# Counter.net
KiCad netlist of a schematic drawn in EAGLE
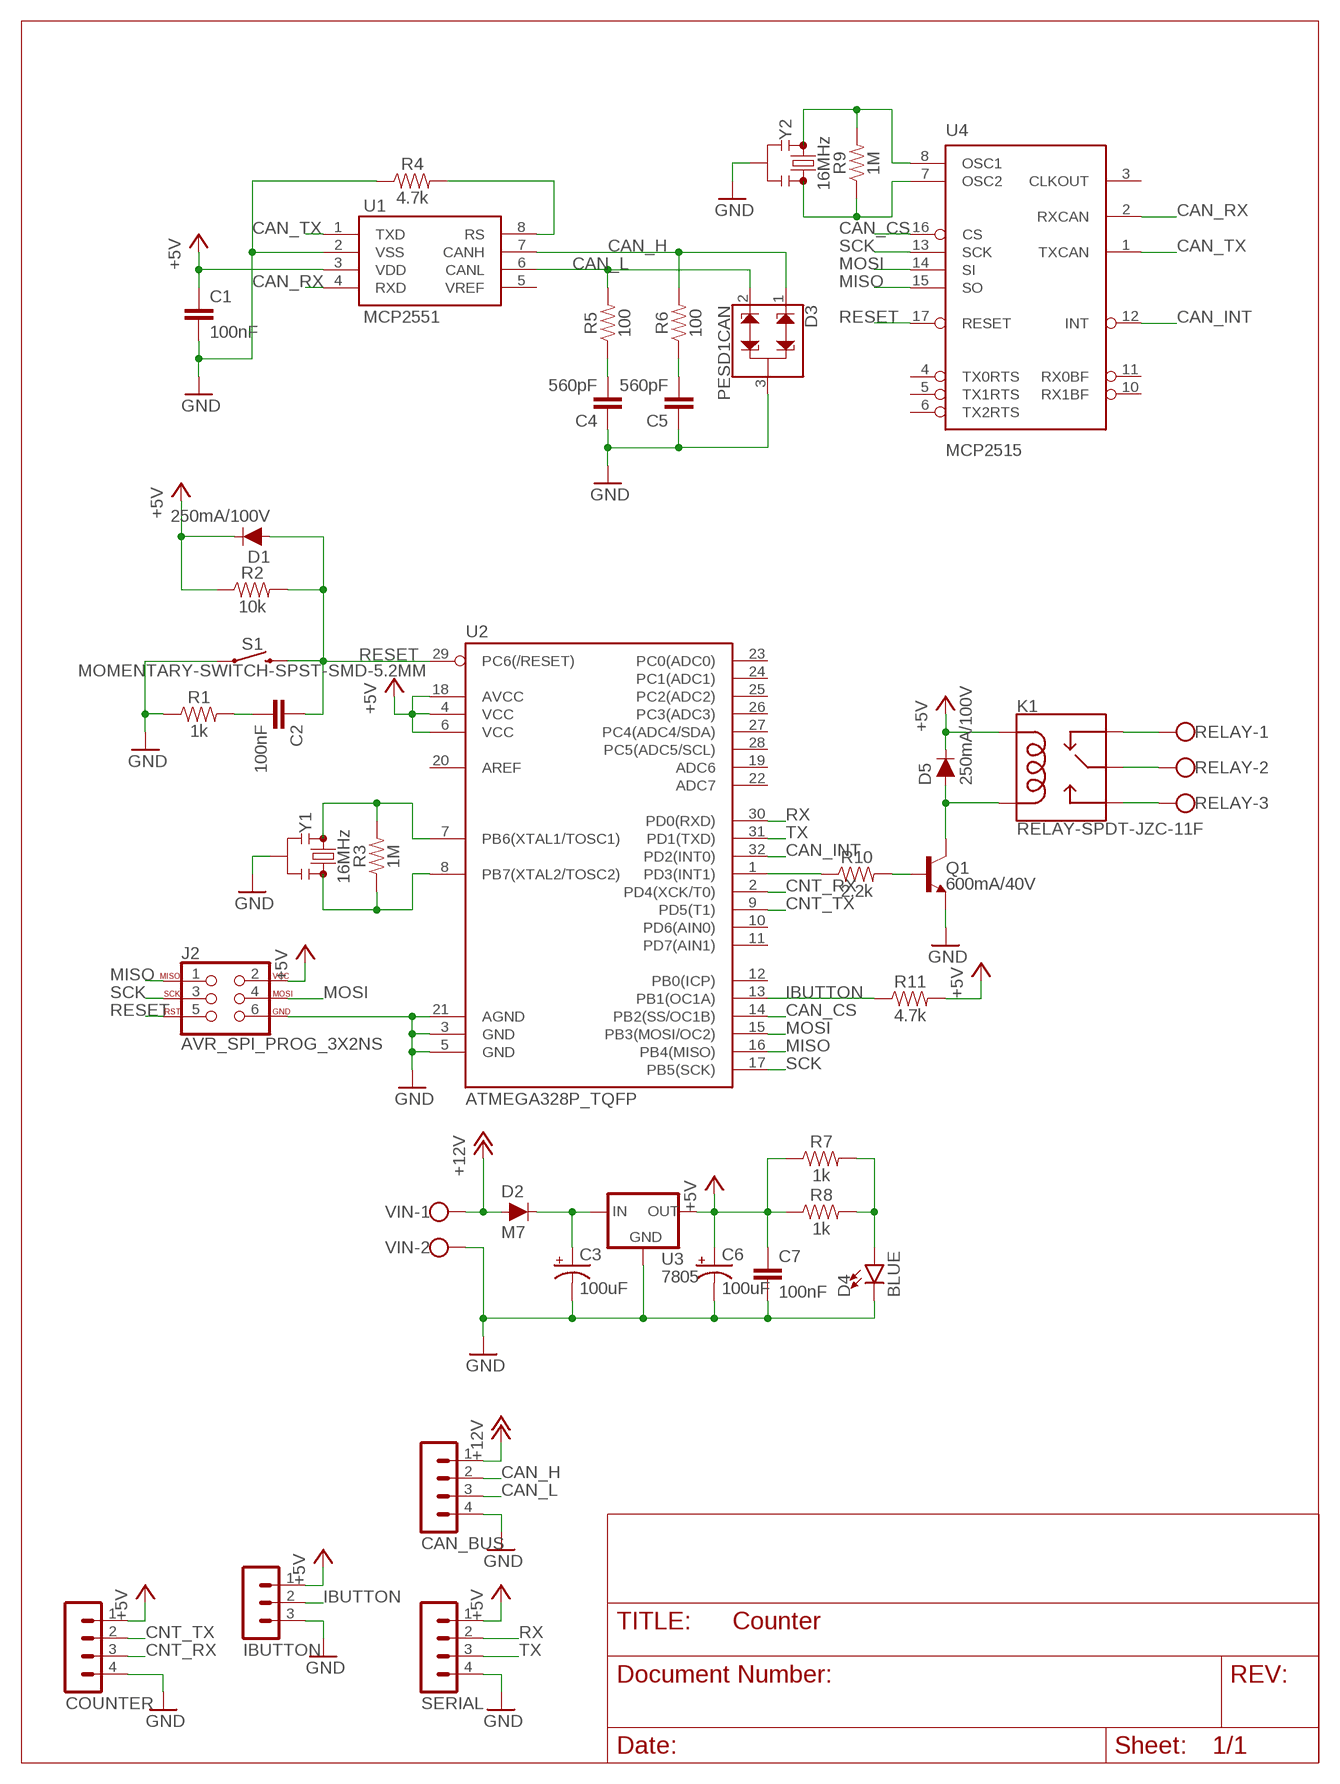
[diagram p0: schematic, sheet 1]

(export (version "E")
  (design (tool "Eeschema 10.0.6"))
  (components
    (comp (ref "C1")
      (value "100nF")
      (footprint "eagle-import:0603")
      (libsource (lib "eagle-import") (part "47NF-0603-25V-5%"))
    )
    (comp (ref "C2")
      (value "100nF")
      (footprint "eagle-import:0603")
      (libsource (lib "eagle-import") (part "47NF-0603-25V-5%"))
    )
    (comp (ref "C3")
      (value "100uF")
      (footprint "eagle-import:PANASONIC_D")
      (libsource (lib "eagle-import") (part "47UF-POLAR-PANASONIC_D-35V-20%"))
    )
    (comp (ref "C4")
      (value "560pF")
      (footprint "eagle-import:0603")
      (libsource (lib "eagle-import") (part "560PF-0603-50V-5%"))
    )
    (comp (ref "C5")
      (value "560pF")
      (footprint "eagle-import:0603")
      (libsource (lib "eagle-import") (part "560PF-0603-50V-5%"))
    )
    (comp (ref "C6")
      (value "100uF")
      (footprint "eagle-import:PANASONIC_D")
      (libsource (lib "eagle-import") (part "47UF-POLAR-PANASONIC_D-35V-20%"))
    )
    (comp (ref "C7")
      (value "100nF")
      (footprint "eagle-import:0603")
      (libsource (lib "eagle-import") (part "47NF-0603-25V-5%"))
    )
    (comp (ref "CAN_BUS")
      (value "MA04-1")
      (footprint "eagle-import:MA04-1")
      (libsource (lib "eagle-import") (part "MA04-1"))
    )
    (comp (ref "COUNTER")
      (value "MA04-1")
      (footprint "eagle-import:MA04-1")
      (libsource (lib "eagle-import") (part "MA04-1"))
    )
    (comp (ref "D1")
      (value "250mA/100V")
      (footprint "eagle-import:SOD-323")
      (libsource (lib "eagle-import") (part "DIODE-BAS16J"))
    )
    (comp (ref "D2")
      (value "M7")
      (footprint "eagle-import:SOD-323")
      (libsource (lib "eagle-import") (part "DIODE-BAS16J"))
    )
    (comp (ref "D3")
      (value "PESD1CAN")
      (footprint "eagle-import:SOT23-3")
      (libsource (lib "eagle-import") (part "PESD1CAN"))
    )
    (comp (ref "D4")
      (value "BLUE")
      (footprint "eagle-import:LED-0603")
      (libsource (lib "eagle-import") (part "LED-BLUE0603"))
    )
    (comp (ref "D5")
      (value "250mA/100V")
      (footprint "eagle-import:SOD-323")
      (libsource (lib "eagle-import") (part "DIODE-BAS16J"))
    )
    (comp (ref "IBUTTON")
      (value "MA03-1")
      (footprint "eagle-import:MA03-1")
      (libsource (lib "eagle-import") (part "MA03-1"))
    )
    (comp (ref "J2")
      (value "AVR_SPI_PROG_3X2NS")
      (footprint "eagle-import:2X3-NS")
      (libsource (lib "eagle-import") (part "AVR_SPI_PROG_3X2NS"))
    )
    (comp (ref "K1")
      (value "RELAY-SPDT-JZC-11F")
      (footprint "eagle-import:RELAY-JZC")
      (libsource (lib "eagle-import") (part "RELAY-SPDT-JZC-11F"))
    )
    (comp (ref "Q1")
      (value "600mA/40V")
      (footprint "eagle-import:SOT23-3")
      (libsource (lib "eagle-import") (part "TRANS_NPN-MMBT2222AL"))
    )
    (comp (ref "R1")
      (value "1k")
      (footprint "eagle-import:0603")
      (libsource (lib "eagle-import") (part "1KOHM-0603-1/10W-1%"))
    )
    (comp (ref "R2")
      (value "10k")
      (footprint "eagle-import:0603")
      (libsource (lib "eagle-import") (part "10KOHM-0603-1/10W-1%"))
    )
    (comp (ref "R3")
      (value "1M")
      (footprint "eagle-import:0603")
      (libsource (lib "eagle-import") (part "1MOHM-0603-1/4W-5%"))
    )
    (comp (ref "R4")
      (value "4.7k")
      (footprint "eagle-import:0603")
      (libsource (lib "eagle-import") (part "4.7KOHM-0603-1/10W-1%"))
    )
    (comp (ref "R5")
      (value "100")
      (footprint "eagle-import:0603")
      (libsource (lib "eagle-import") (part "100OHM-0603-1/10W-1%"))
    )
    (comp (ref "R6")
      (value "100")
      (footprint "eagle-import:0603")
      (libsource (lib "eagle-import") (part "100OHM-0603-1/10W-1%"))
    )
    (comp (ref "R7")
      (value "1k")
      (footprint "eagle-import:0603")
      (libsource (lib "eagle-import") (part "1KOHM-0603-1/10W-1%"))
    )
    (comp (ref "R8")
      (value "1k")
      (footprint "eagle-import:0603")
      (libsource (lib "eagle-import") (part "1KOHM-0603-1/10W-1%"))
    )
    (comp (ref "R9")
      (value "1M")
      (footprint "eagle-import:0603")
      (libsource (lib "eagle-import") (part "1MOHM-0603-1/4W-5%"))
    )
    (comp (ref "R10")
      (value "2.2k")
      (footprint "eagle-import:0603")
      (libsource (lib "eagle-import") (part "2.2KOHM-0603-1/10W-1%"))
    )
    (comp (ref "R11")
      (value "4.7k")
      (footprint "eagle-import:0603")
      (libsource (lib "eagle-import") (part "4.7KOHM-0603-1/10W-1%"))
    )
    (comp (ref "RELAY")
      (value "W237-103")
      (footprint "eagle-import:W237-103")
      (fields (field (name "MPN") "237-103"))
      (libsource (lib "eagle-import") (part "W237-103"))
    )
    (comp (ref "S1")
      (value "MOMENTARY-SWITCH-SPST-SMD-5.2MM")
      (footprint "eagle-import:TACTILE_SWITCH_SMD_5.2MM")
      (libsource (lib "eagle-import") (part "MOMENTARY-SWITCH-SPST-SMD-5.2MM"))
    )
    (comp (ref "SERIAL")
      (value "MA04-1")
      (footprint "eagle-import:MA04-1")
      (libsource (lib "eagle-import") (part "MA04-1"))
    )
    (comp (ref "U1")
      (value "MCP2551")
      (footprint "eagle-import:SO08")
      (libsource (lib "eagle-import") (part "MCP2551"))
    )
    (comp (ref "U2")
      (value "ATMEGA328P_TQFP")
      (footprint "eagle-import:TQFP32-08")
      (libsource (lib "eagle-import") (part "ATMEGA328P_TQFP"))
    )
    (comp (ref "U3")
      (value "7805")
      (footprint "eagle-import:TO-252")
      (libsource (lib "eagle-import") (part "V_REG_78XX7812"))
    )
    (comp (ref "U4")
      (value "MCP2515")
      (footprint "eagle-import:SO18W")
      (libsource (lib "eagle-import") (part "MCP2515(MCP2510)SO"))
    )
    (comp (ref "VIN")
      (value "W237-102")
      (footprint "eagle-import:W237-102")
      (fields (field (name "MPN") "237-102"))
      (libsource (lib "eagle-import") (part "W237-102"))
    )
    (comp (ref "Y1")
      (value "16MHz")
      (footprint "eagle-import:RESONATOR-SMD-3.2X1.3")
      (libsource (lib "eagle-import") (part "RESONATOR-16MHZSMD_3.2X1.3"))
    )
    (comp (ref "Y2")
      (value "16MHz")
      (footprint "eagle-import:RESONATOR-SMD-3.2X1.3")
      (libsource (lib "eagle-import") (part "RESONATOR-16MHZSMD_3.2X1.3"))
    )
  )
  (nets
    (net (code "1") (name "+5V") (class "Default")
      (node (ref "C1") (pin "1") (pinfunction "1_1") (pintype "passive"))
      (node (ref "C6") (pin "+") (pinfunction "+_+") (pintype "passive"))
      (node (ref "C7") (pin "1") (pinfunction "1_1") (pintype "passive"))
      (node (ref "COUNTER") (pin "1") (pinfunction "1_1") (pintype "passive"))
      (node (ref "D1") (pin "C") (pinfunction "C_C") (pintype "passive"))
      (node (ref "D5") (pin "C") (pinfunction "C_C") (pintype "passive"))
      (node (ref "IBUTTON") (pin "1") (pinfunction "1_1") (pintype "passive"))
      (node (ref "J2") (pin "2") (pinfunction "2_2") (pintype "passive"))
      (node (ref "K1") (pin "5") (pinfunction "COIL1_5") (pintype "bidirectional"))
      (node (ref "R11") (pin "2") (pinfunction "2_2") (pintype "passive"))
      (node (ref "R2") (pin "1") (pinfunction "1_1") (pintype "passive"))
      (node (ref "R7") (pin "1") (pinfunction "1_1") (pintype "passive"))
      (node (ref "R8") (pin "1") (pinfunction "1_1") (pintype "passive"))
      (node (ref "SERIAL") (pin "1") (pinfunction "1_1") (pintype "passive"))
      (node (ref "U1") (pin "3") (pinfunction "VDD_3") (pintype "bidirectional"))
      (node (ref "U2") (pin "18") (pinfunction "AVCC_18") (pintype "bidirectional"))
      (node (ref "U2") (pin "4") (pinfunction "VCC_4") (pintype "bidirectional"))
      (node (ref "U2") (pin "6") (pinfunction "VCC_6") (pintype "bidirectional"))
      (node (ref "U3") (pin "2") (pinfunction "OUT_2") (pintype "passive"))
    )
    (net (code "2") (name "+12V") (class "Default")
      (node (ref "CAN_BUS") (pin "1") (pinfunction "1_1") (pintype "passive"))
      (node (ref "D2") (pin "A") (pinfunction "A_A") (pintype "passive"))
      (node (ref "VIN") (pin "1") (pinfunction "KL_1") (pintype "passive"))
    )
    (net (code "3") (name "/CAN_CS") (class "Default")
      (node (ref "U2") (pin "14") (pinfunction "PB2(SS/OC1B)_14") (pintype "bidirectional"))
      (node (ref "U4") (pin "16") (pinfunction "CS_16") (pintype "input"))
    )
    (net (code "4") (name "/CAN_H") (class "Default")
      (node (ref "CAN_BUS") (pin "2") (pinfunction "2_2") (pintype "passive"))
      (node (ref "D3") (pin "1") (pinfunction "1_1") (pintype "bidirectional"))
      (node (ref "R6") (pin "2") (pinfunction "2_2") (pintype "passive"))
      (node (ref "U1") (pin "7") (pinfunction "CANH_7") (pintype "bidirectional"))
    )
    (net (code "5") (name "/CAN_INT") (class "Default")
      (node (ref "U2") (pin "32") (pinfunction "PD2(INT0)_32") (pintype "bidirectional"))
      (node (ref "U4") (pin "12") (pinfunction "INT_12") (pintype "output"))
    )
    (net (code "6") (name "/CAN_L") (class "Default")
      (node (ref "CAN_BUS") (pin "3") (pinfunction "3_3") (pintype "passive"))
      (node (ref "D3") (pin "2") (pinfunction "2_2") (pintype "bidirectional"))
      (node (ref "R5") (pin "2") (pinfunction "2_2") (pintype "passive"))
      (node (ref "U1") (pin "6") (pinfunction "CANL_6") (pintype "bidirectional"))
    )
    (net (code "7") (name "/CAN_RX") (class "Default")
      (node (ref "U1") (pin "4") (pinfunction "RXD_4") (pintype "bidirectional"))
      (node (ref "U4") (pin "2") (pinfunction "RXCAN_2") (pintype "input"))
    )
    (net (code "8") (name "/CAN_TX") (class "Default")
      (node (ref "U1") (pin "1") (pinfunction "TXD_1") (pintype "bidirectional"))
      (node (ref "U4") (pin "1") (pinfunction "TXCAN_1") (pintype "output"))
    )
    (net (code "9") (name "/CNT_RX") (class "Default")
      (node (ref "COUNTER") (pin "3") (pinfunction "3_3") (pintype "passive"))
      (node (ref "U2") (pin "2") (pinfunction "PD4(XCK/T0)_2") (pintype "bidirectional"))
    )
    (net (code "10") (name "/CNT_TX") (class "Default")
      (node (ref "COUNTER") (pin "2") (pinfunction "2_2") (pintype "passive"))
      (node (ref "U2") (pin "9") (pinfunction "PD5(T1)_9") (pintype "bidirectional"))
    )
    (net (code "11") (name "/IBUTTON") (class "Default")
      (node (ref "IBUTTON") (pin "2") (pinfunction "2_2") (pintype "passive"))
      (node (ref "R11") (pin "1") (pinfunction "1_1") (pintype "passive"))
      (node (ref "U2") (pin "13") (pinfunction "PB1(OC1A)_13") (pintype "bidirectional"))
    )
    (net (code "12") (name "/MISO") (class "Default")
      (node (ref "J2") (pin "1") (pinfunction "1_1") (pintype "passive"))
      (node (ref "U2") (pin "16") (pinfunction "PB4(MISO)_16") (pintype "bidirectional"))
      (node (ref "U4") (pin "15") (pinfunction "SO_15") (pintype "output"))
    )
    (net (code "13") (name "/MOSI") (class "Default")
      (node (ref "J2") (pin "4") (pinfunction "4_4") (pintype "passive"))
      (node (ref "U2") (pin "15") (pinfunction "PB3(MOSI/OC2)_15") (pintype "bidirectional"))
      (node (ref "U4") (pin "14") (pinfunction "SI_14") (pintype "input"))
    )
    (net (code "14") (name "/RESET") (class "Default")
      (node (ref "C2") (pin "1") (pinfunction "1_1") (pintype "passive"))
      (node (ref "D1") (pin "A") (pinfunction "A_A") (pintype "passive"))
      (node (ref "J2") (pin "5") (pinfunction "5_5") (pintype "passive"))
      (node (ref "R2") (pin "2") (pinfunction "2_2") (pintype "passive"))
      (node (ref "S1") (pin "3") (pinfunction "2_3") (pintype "passive"))
      (node (ref "U2") (pin "29") (pinfunction "PC6(/RESET)_29") (pintype "bidirectional"))
      (node (ref "U4") (pin "17") (pinfunction "RESET_17") (pintype "input"))
    )
    (net (code "15") (name "/RX") (class "Default")
      (node (ref "SERIAL") (pin "2") (pinfunction "2_2") (pintype "passive"))
      (node (ref "U2") (pin "30") (pinfunction "PD0(RXD)_30") (pintype "bidirectional"))
    )
    (net (code "16") (name "/SCK") (class "Default")
      (node (ref "J2") (pin "3") (pinfunction "3_3") (pintype "passive"))
      (node (ref "U2") (pin "17") (pinfunction "PB5(SCK)_17") (pintype "bidirectional"))
      (node (ref "U4") (pin "13") (pinfunction "SCK_13") (pintype "input"))
    )
    (net (code "17") (name "/TX") (class "Default")
      (node (ref "SERIAL") (pin "3") (pinfunction "3_3") (pintype "passive"))
      (node (ref "U2") (pin "31") (pinfunction "PD1(TXD)_31") (pintype "bidirectional"))
    )
    (net (code "18") (name "GND") (class "Default")
      (node (ref "C1") (pin "2") (pinfunction "2_2") (pintype "passive"))
      (node (ref "C3") (pin "-") (pinfunction "-_-") (pintype "passive"))
      (node (ref "C4") (pin "1") (pinfunction "1_1") (pintype "passive"))
      (node (ref "C5") (pin "1") (pinfunction "1_1") (pintype "passive"))
      (node (ref "C6") (pin "-") (pinfunction "-_-") (pintype "passive"))
      (node (ref "C7") (pin "2") (pinfunction "2_2") (pintype "passive"))
      (node (ref "CAN_BUS") (pin "4") (pinfunction "4_4") (pintype "passive"))
      (node (ref "COUNTER") (pin "4") (pinfunction "4_4") (pintype "passive"))
      (node (ref "D3") (pin "3") (pinfunction "3_3") (pintype "bidirectional"))
      (node (ref "D4") (pin "C") (pinfunction "C_C") (pintype "passive"))
      (node (ref "IBUTTON") (pin "3") (pinfunction "3_3") (pintype "passive"))
      (node (ref "J2") (pin "6") (pinfunction "6_6") (pintype "passive"))
      (node (ref "Q1") (pin "2") (pinfunction "E_2") (pintype "passive"))
      (node (ref "R1") (pin "1") (pinfunction "1_1") (pintype "passive"))
      (node (ref "R4") (pin "1") (pinfunction "1_1") (pintype "passive"))
      (node (ref "S1") (pin "1") (pinfunction "1_1") (pintype "passive"))
      (node (ref "SERIAL") (pin "4") (pinfunction "4_4") (pintype "passive"))
      (node (ref "U1") (pin "2") (pinfunction "VSS_2") (pintype "bidirectional"))
      (node (ref "U2") (pin "21") (pinfunction "AGND_21") (pintype "bidirectional"))
      (node (ref "U2") (pin "3") (pinfunction "GND_3") (pintype "bidirectional"))
      (node (ref "U2") (pin "5") (pinfunction "GND_5") (pintype "bidirectional"))
      (node (ref "U3") (pin "3") (pinfunction "GND_3") (pintype "input"))
      (node (ref "VIN") (pin "2") (pinfunction "KL_2") (pintype "passive"))
      (node (ref "Y1") (pin "2") (pinfunction "2_2") (pintype "passive"))
      (node (ref "Y2") (pin "2") (pinfunction "2_2") (pintype "passive"))
    )
    (net (code "19") (name "Net-(C2-Pad2)") (class "Default")
      (node (ref "C2") (pin "2") (pinfunction "2_2") (pintype "passive"))
      (node (ref "R1") (pin "2") (pinfunction "2_2") (pintype "passive"))
    )
    (net (code "20") (name "Net-(C4-Pad2)") (class "Default")
      (node (ref "C4") (pin "2") (pinfunction "2_2") (pintype "passive"))
      (node (ref "R5") (pin "1") (pinfunction "1_1") (pintype "passive"))
    )
    (net (code "21") (name "Net-(C5-Pad2)") (class "Default")
      (node (ref "C5") (pin "2") (pinfunction "2_2") (pintype "passive"))
      (node (ref "R6") (pin "1") (pinfunction "1_1") (pintype "passive"))
    )
    (net (code "22") (name "Net-(D4-PadA)") (class "Default")
      (node (ref "D4") (pin "A") (pinfunction "A_A") (pintype "passive"))
      (node (ref "R7") (pin "2") (pinfunction "2_2") (pintype "passive"))
      (node (ref "R8") (pin "2") (pinfunction "2_2") (pintype "passive"))
    )
    (net (code "23") (name "Net-(K1-COIL2)") (class "Default")
      (node (ref "D5") (pin "A") (pinfunction "A_A") (pintype "passive"))
      (node (ref "K1") (pin "1") (pinfunction "COIL2_1") (pintype "bidirectional"))
      (node (ref "Q1") (pin "3") (pinfunction "C_3") (pintype "passive"))
    )
    (net (code "24") (name "Net-(K1-MAIN)") (class "Default")
      (node (ref "K1") (pin "4") (pinfunction "MAIN_4") (pintype "bidirectional"))
      (node (ref "RELAY") (pin "2") (pinfunction "KL_2") (pintype "passive"))
    )
    (net (code "25") (name "Net-(K1-NC)") (class "Default")
      (node (ref "K1") (pin "2") (pinfunction "NC_2") (pintype "bidirectional"))
      (node (ref "RELAY") (pin "1") (pinfunction "KL_1") (pintype "passive"))
    )
    (net (code "26") (name "Net-(K1-NO)") (class "Default")
      (node (ref "K1") (pin "3") (pinfunction "NO_3") (pintype "bidirectional"))
      (node (ref "RELAY") (pin "3") (pinfunction "KL_3") (pintype "passive"))
    )
    (net (code "27") (name "Net-(Q1-B)") (class "Default")
      (node (ref "Q1") (pin "1") (pinfunction "B_1") (pintype "passive"))
      (node (ref "R10") (pin "2") (pinfunction "2_2") (pintype "passive"))
    )
    (net (code "28") (name "Net-(U1-RS)") (class "Default")
      (node (ref "R4") (pin "2") (pinfunction "2_2") (pintype "passive"))
      (node (ref "U1") (pin "8") (pinfunction "RS_8") (pintype "bidirectional"))
    )
    (net (code "29") (name "Net-(U2-PB6(XTAL1{slash}TOSC1))") (class "Default")
      (node (ref "R3") (pin "2") (pinfunction "2_2") (pintype "passive"))
      (node (ref "U2") (pin "7") (pinfunction "PB6(XTAL1/TOSC1)_7") (pintype "bidirectional"))
      (node (ref "Y1") (pin "1") (pinfunction "1_1") (pintype "passive"))
    )
    (net (code "30") (name "Net-(U2-PB7(XTAL2{slash}TOSC2))") (class "Default")
      (node (ref "R3") (pin "1") (pinfunction "1_1") (pintype "passive"))
      (node (ref "U2") (pin "8") (pinfunction "PB7(XTAL2/TOSC2)_8") (pintype "bidirectional"))
      (node (ref "Y1") (pin "3") (pinfunction "3_3") (pintype "passive"))
    )
    (net (code "31") (name "Net-(U2-PD3(INT1))") (class "Default")
      (node (ref "R10") (pin "1") (pinfunction "1_1") (pintype "passive"))
      (node (ref "U2") (pin "1") (pinfunction "PD3(INT1)_1") (pintype "bidirectional"))
    )
    (net (code "32") (name "Net-(U3-IN)") (class "Default")
      (node (ref "C3") (pin "+") (pinfunction "+_+") (pintype "passive"))
      (node (ref "D2") (pin "C") (pinfunction "C_C") (pintype "passive"))
      (node (ref "U3") (pin "1") (pinfunction "IN_1") (pintype "input"))
    )
    (net (code "33") (name "Net-(U4A-OSC1)") (class "Default")
      (node (ref "R9") (pin "2") (pinfunction "2_2") (pintype "passive"))
      (node (ref "U4") (pin "8") (pinfunction "OSC1_8") (pintype "input"))
      (node (ref "Y2") (pin "1") (pinfunction "1_1") (pintype "passive"))
    )
    (net (code "34") (name "Net-(U4A-OSC2)") (class "Default")
      (node (ref "R9") (pin "1") (pinfunction "1_1") (pintype "passive"))
      (node (ref "U4") (pin "7") (pinfunction "OSC2_7") (pintype "output"))
      (node (ref "Y2") (pin "3") (pinfunction "3_3") (pintype "passive"))
    )
    (net (code "35") (name "unconnected-(U1-VREF-Pad5)") (class "Default")
      (node (ref "U1") (pin "5") (pinfunction "VREF_5") (pintype "bidirectional"))
    )
    (net (code "36") (name "unconnected-(U2-ADC6-Pad19)") (class "Default")
      (node (ref "U2") (pin "19") (pinfunction "ADC6_19") (pintype "bidirectional"))
    )
    (net (code "37") (name "unconnected-(U2-ADC7-Pad22)") (class "Default")
      (node (ref "U2") (pin "22") (pinfunction "ADC7_22") (pintype "bidirectional"))
    )
    (net (code "38") (name "unconnected-(U2-AREF-Pad20)") (class "Default")
      (node (ref "U2") (pin "20") (pinfunction "AREF_20") (pintype "bidirectional"))
    )
    (net (code "39") (name "unconnected-(U2-PB0(ICP)-Pad12)") (class "Default")
      (node (ref "U2") (pin "12") (pinfunction "PB0(ICP)_12") (pintype "bidirectional"))
    )
    (net (code "40") (name "unconnected-(U2-PC0(ADC0)-Pad23)") (class "Default")
      (node (ref "U2") (pin "23") (pinfunction "PC0(ADC0)_23") (pintype "bidirectional"))
    )
    (net (code "41") (name "unconnected-(U2-PC1(ADC1)-Pad24)") (class "Default")
      (node (ref "U2") (pin "24") (pinfunction "PC1(ADC1)_24") (pintype "bidirectional"))
    )
    (net (code "42") (name "unconnected-(U2-PC2(ADC2)-Pad25)") (class "Default")
      (node (ref "U2") (pin "25") (pinfunction "PC2(ADC2)_25") (pintype "bidirectional"))
    )
    (net (code "43") (name "unconnected-(U2-PC3(ADC3)-Pad26)") (class "Default")
      (node (ref "U2") (pin "26") (pinfunction "PC3(ADC3)_26") (pintype "bidirectional"))
    )
    (net (code "44") (name "unconnected-(U2-PC4(ADC4{slash}SDA)-Pad27)") (class "Default")
      (node (ref "U2") (pin "27") (pinfunction "PC4(ADC4/SDA)_27") (pintype "bidirectional"))
    )
    (net (code "45") (name "unconnected-(U2-PC5(ADC5{slash}SCL)-Pad28)") (class "Default")
      (node (ref "U2") (pin "28") (pinfunction "PC5(ADC5/SCL)_28") (pintype "bidirectional"))
    )
    (net (code "46") (name "unconnected-(U2-PD6(AIN0)-Pad10)") (class "Default")
      (node (ref "U2") (pin "10") (pinfunction "PD6(AIN0)_10") (pintype "bidirectional"))
    )
    (net (code "47") (name "unconnected-(U2-PD7(AIN1)-Pad11)") (class "Default")
      (node (ref "U2") (pin "11") (pinfunction "PD7(AIN1)_11") (pintype "bidirectional"))
    )
    (net (code "48") (name "unconnected-(U4A-CLKOUT-Pad3)") (class "Default")
      (node (ref "U4") (pin "3") (pinfunction "CLKOUT_3") (pintype "output"))
    )
    (net (code "49") (name "unconnected-(U4A-RX0BF-Pad11)") (class "Default")
      (node (ref "U4") (pin "11") (pinfunction "RX0BF_11") (pintype "output"))
    )
    (net (code "50") (name "unconnected-(U4A-RX1BF-Pad10)") (class "Default")
      (node (ref "U4") (pin "10") (pinfunction "RX1BF_10") (pintype "output"))
    )
    (net (code "51") (name "unconnected-(U4A-TX0RTS-Pad4)") (class "Default")
      (node (ref "U4") (pin "4") (pinfunction "TX0RTS_4") (pintype "input"))
    )
    (net (code "52") (name "unconnected-(U4A-TX1RTS-Pad5)") (class "Default")
      (node (ref "U4") (pin "5") (pinfunction "TX1RTS_5") (pintype "input"))
    )
    (net (code "53") (name "unconnected-(U4A-TX2RTS-Pad6)") (class "Default")
      (node (ref "U4") (pin "6") (pinfunction "TX2RTS_6") (pintype "input"))
    )
  )
)
